# EEPROM.net
KiCad netlist of a schematic drawn in Altium Designer
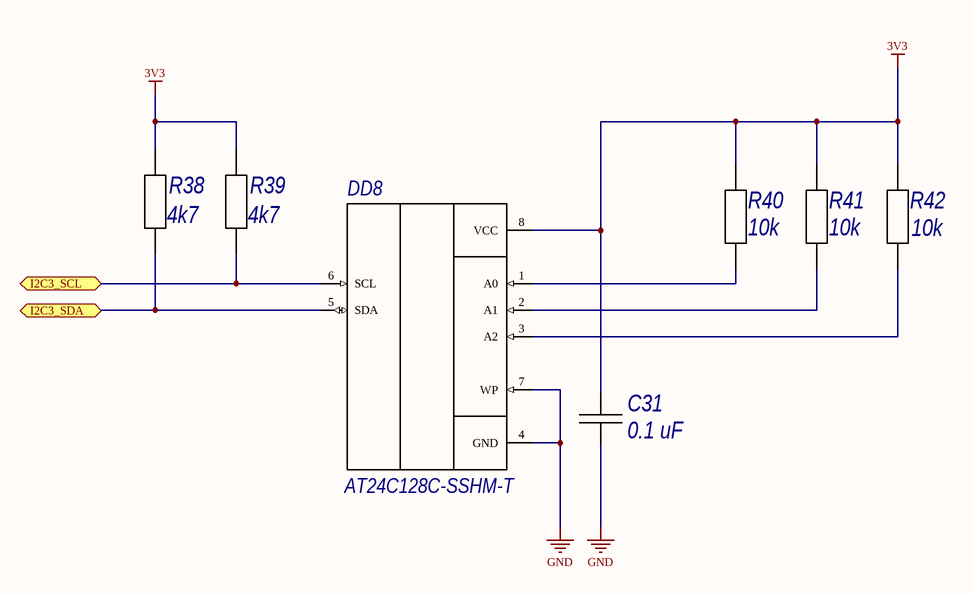
[diagram p0: EEPROM.SchDoc]

(export (version "E")
  (design (tool "Eeschema 10.0.6"))
  (components
    (comp (ref "C31")
      (value "0.1 uF")
      (footprint "C0805C")
      (fields (field (name "PUBLISHER") "Andrew Danich"))
      (libsource (lib "PA_control_board") (part "CAP_0805"))
    )
    (comp (ref "DD8")
      (value "AT24C128C-SSHM-T")
      (footprint "SOIC127P600X175-8N")
      (description "EEPROM Memory IC 128Kb _16K x 8_ IÂ²C 1MHz 550ns 8-SOIC")
      (fields (field (name "MF") "Microchip"))
      (libsource (lib "PA_control_board") (part "AT24C128C-SSHM-T"))
    )
    (comp (ref "R38")
      (value "4k7")
      (footprint "C0805R")
      (fields (field (name "PUBLISHER") "Andrew Danich"))
      (libsource (lib "PA_control_board") (part "RES_0805"))
    )
    (comp (ref "R39")
      (value "4k7")
      (footprint "C0805R")
      (fields (field (name "PUBLISHER") "Andrew Danich"))
      (libsource (lib "PA_control_board") (part "RES_0805"))
    )
    (comp (ref "R40")
      (value "10k")
      (footprint "C0805R")
      (fields (field (name "PUBLISHER") "Andrew Danich"))
      (libsource (lib "PA_control_board") (part "RES_0805"))
    )
    (comp (ref "R41")
      (value "10k")
      (footprint "C0805R")
      (fields (field (name "PUBLISHER") "Andrew Danich"))
      (libsource (lib "PA_control_board") (part "RES_0805"))
    )
    (comp (ref "R42")
      (value "10k")
      (footprint "C0805R")
      (fields (field (name "PUBLISHER") "Andrew Danich"))
      (libsource (lib "PA_control_board") (part "RES_0805"))
    )
  )
  (nets
    (net (code "1") (name "/I2C3_SCL") (class "Default")
      (node (ref "DD8") (pin "6") (pinfunction "SCL_6") (pintype "input"))
      (node (ref "R39") (pin "1") (pinfunction "1_1") (pintype "passive"))
    )
    (net (code "2") (name "/I2C3_SDA") (class "Default")
      (node (ref "DD8") (pin "5") (pinfunction "SDA_5") (pintype "bidirectional"))
      (node (ref "R38") (pin "1") (pinfunction "1_1") (pintype "passive"))
    )
    (net (code "3") (name "3V3") (class "Default")
      (node (ref "C31") (pin "2") (pinfunction "2_2") (pintype "passive"))
      (node (ref "DD8") (pin "8") (pinfunction "VCC_8") (pintype "power_in"))
      (node (ref "R38") (pin "2") (pinfunction "2_2") (pintype "passive"))
      (node (ref "R39") (pin "2") (pinfunction "2_2") (pintype "passive"))
      (node (ref "R40") (pin "2") (pinfunction "2_2") (pintype "passive"))
      (node (ref "R41") (pin "2") (pinfunction "2_2") (pintype "passive"))
      (node (ref "R42") (pin "2") (pinfunction "2_2") (pintype "passive"))
    )
    (net (code "4") (name "GND") (class "Default")
      (node (ref "C31") (pin "1") (pinfunction "1_1") (pintype "passive"))
      (node (ref "DD8") (pin "4") (pinfunction "GND_4") (pintype "passive"))
      (node (ref "DD8") (pin "7") (pinfunction "WP_7") (pintype "input"))
    )
    (net (code "5") (name "Net-(DD8-A0)") (class "Default")
      (node (ref "DD8") (pin "1") (pinfunction "A0_1") (pintype "input"))
      (node (ref "R40") (pin "1") (pinfunction "1_1") (pintype "passive"))
    )
    (net (code "6") (name "Net-(DD8-A1)") (class "Default")
      (node (ref "DD8") (pin "2") (pinfunction "A1_2") (pintype "input"))
      (node (ref "R41") (pin "1") (pinfunction "1_1") (pintype "passive"))
    )
    (net (code "7") (name "Net-(DD8-A2)") (class "Default")
      (node (ref "DD8") (pin "3") (pinfunction "A2_3") (pintype "input"))
      (node (ref "R42") (pin "1") (pinfunction "1_1") (pintype "passive"))
    )
  )
)
